# PERIPHERALS.net
KiCad netlist of a schematic drawn in Altium Designer
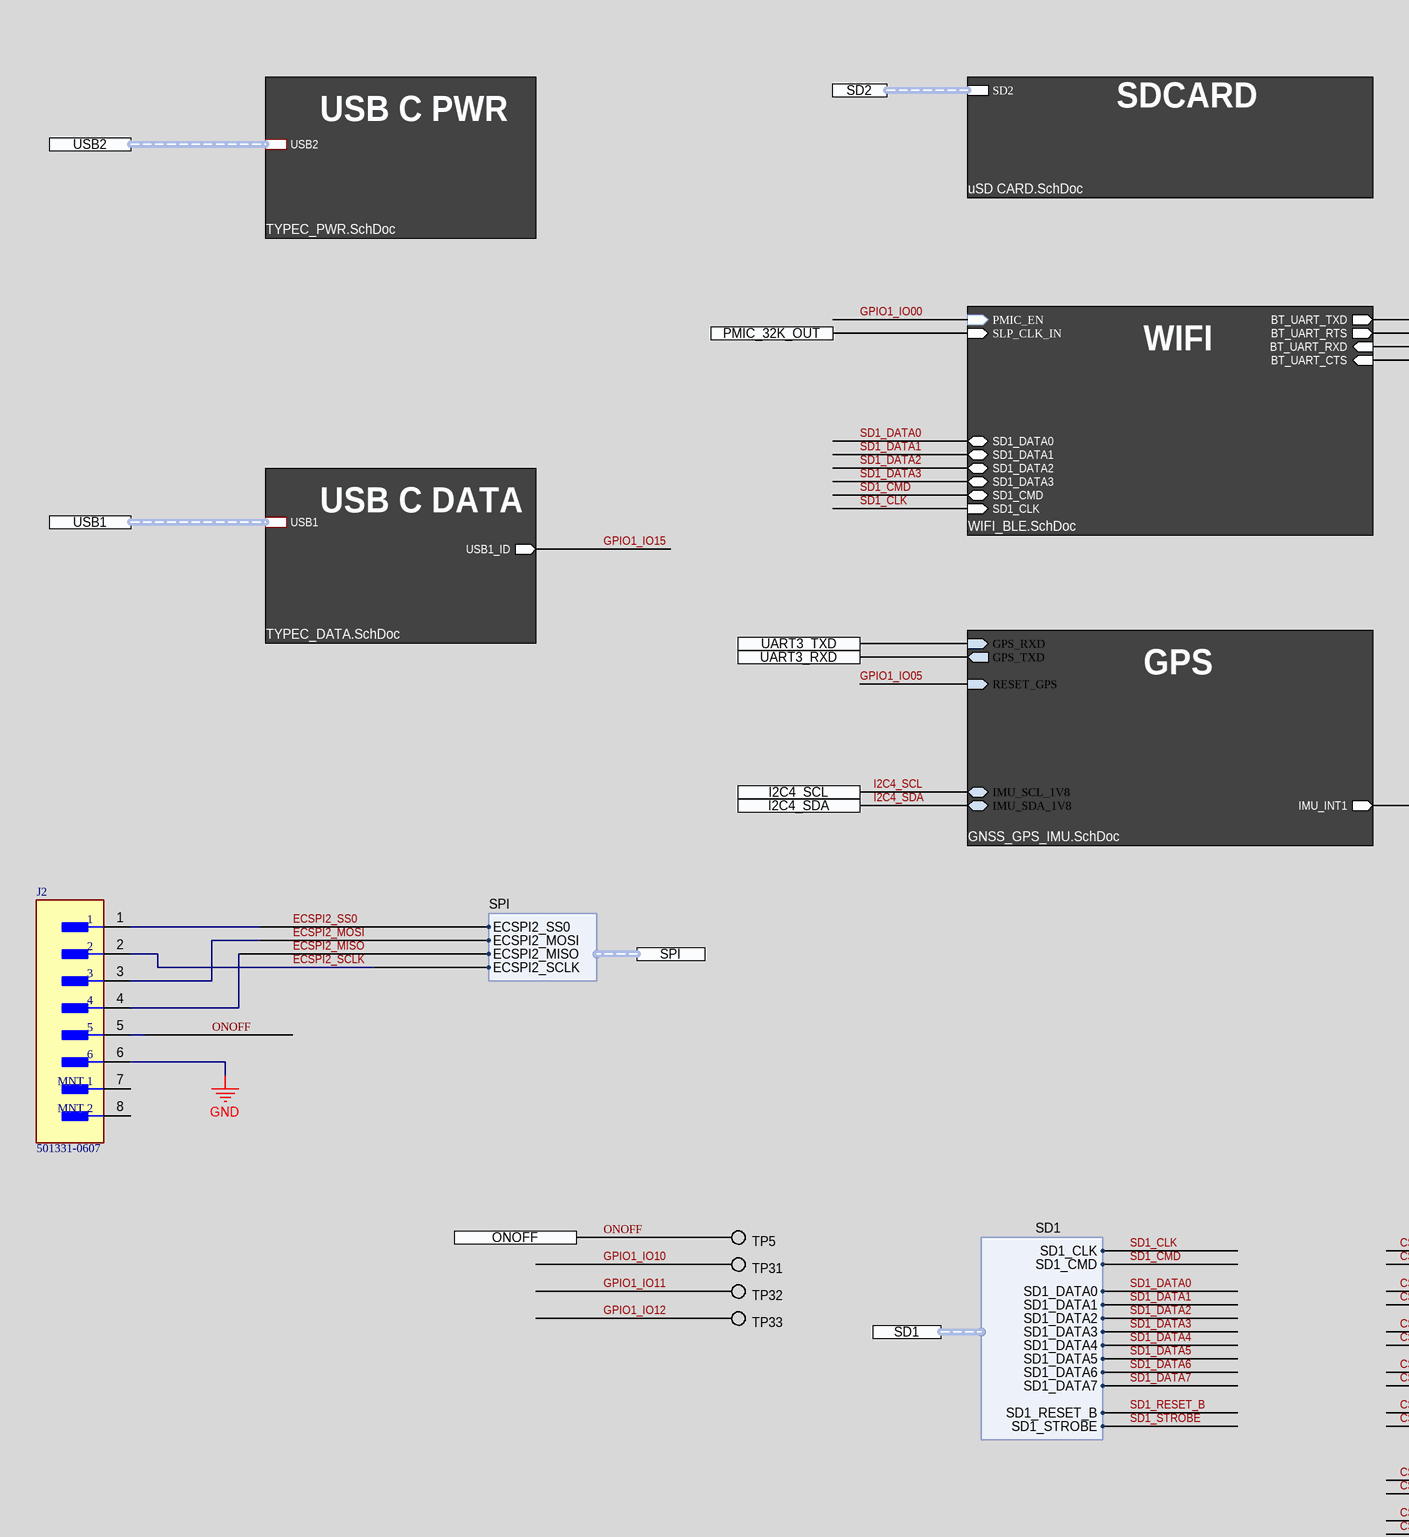
[diagram p0: PERIPHERALS.SchDoc, left]
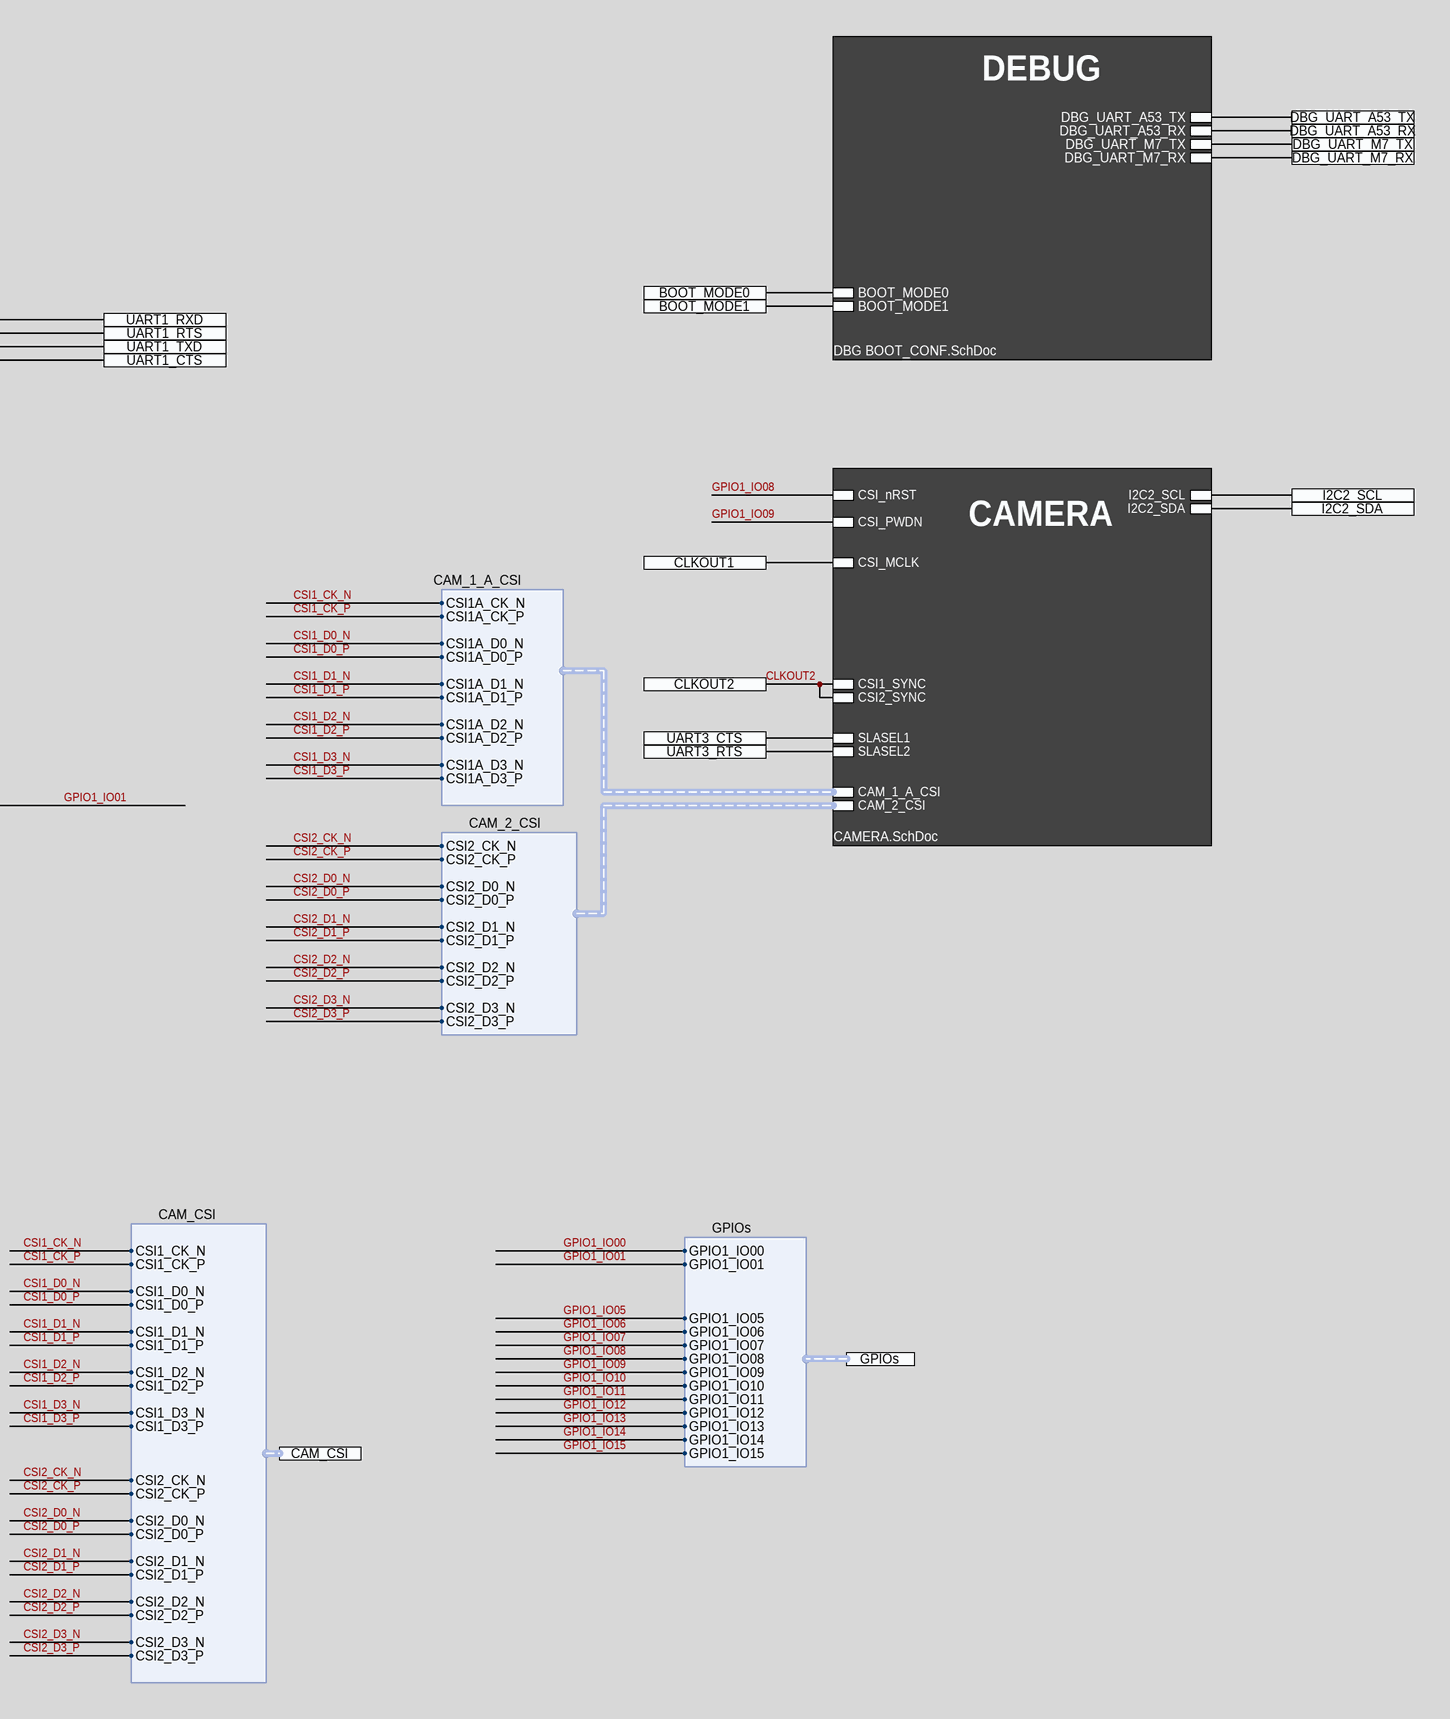
[diagram p1: PERIPHERALS.SchDoc, right]

(export (version "E")
  (design (tool "Eeschema 10.0.6"))
  (components
    (comp (ref "J2")
      (value "501331-0607")
      (footprint "FP-501331-0607-MFG")
      (description "CONN HEADER SMD 6POS 1MM")
      (libsource (lib "Altium Content Vault") (part "2bd7785e6f3406c6201afa29ba70f07"))
    )
    (comp (ref "TP5")
      (value "NO COMPONENT")
      (footprint "TP_PAD_0.5MM_SMD_ROUND")
      (description "Test Point, SMD pad, round, 1.5mm, 1.6mm, 3mm diameter")
      (libsource (lib "Electronic Devices_LIB") (part "TP_PAD_SMD_SMALL"))
    )
    (comp (ref "TP31")
      (value "NO COMPONENT")
      (footprint "TP_PAD_0.5MM_SMD_ROUND")
      (description "Test Point, SMD pad, round, 1.5mm, 1.6mm, 3mm diameter")
      (libsource (lib "Electronic Devices_LIB") (part "TP_PAD_SMD_SMALL"))
    )
    (comp (ref "TP32")
      (value "NO COMPONENT")
      (footprint "TP_PAD_0.5MM_SMD_ROUND")
      (description "Test Point, SMD pad, round, 1.5mm, 1.6mm, 3mm diameter")
      (libsource (lib "Electronic Devices_LIB") (part "TP_PAD_SMD_SMALL"))
    )
    (comp (ref "TP33")
      (value "NO COMPONENT")
      (footprint "TP_PAD_0.5MM_SMD_ROUND")
      (description "Test Point, SMD pad, round, 1.5mm, 1.6mm, 3mm diameter")
      (libsource (lib "Electronic Devices_LIB") (part "TP_PAD_SMD_SMALL"))
    )
  )
  (nets
    (net (code "38") (name "/ECSPI2_MISO") (class "Default")
      (node (ref "J2") (pin "4") (pinfunction "4_4") (pintype "passive"))
    )
    (net (code "39") (name "/ECSPI2_MOSI") (class "Default")
      (node (ref "J2") (pin "3") (pinfunction "3_3") (pintype "passive"))
    )
    (net (code "40") (name "/ECSPI2_SCLK") (class "Default")
      (node (ref "J2") (pin "2") (pinfunction "2_2") (pintype "passive"))
    )
    (net (code "41") (name "/ECSPI2_SS0") (class "Default")
      (node (ref "J2") (pin "1") (pinfunction "1_1") (pintype "passive"))
    )
    (net (code "49") (name "/GPIO1_IO10") (class "Default")
      (node (ref "TP31") (pin "1") (pinfunction "1_1") (pintype "passive"))
    )
    (net (code "50") (name "/GPIO1_IO11") (class "Default")
      (node (ref "TP32") (pin "1") (pinfunction "1_1") (pintype "passive"))
    )
    (net (code "51") (name "/GPIO1_IO12") (class "Default")
      (node (ref "TP33") (pin "1") (pinfunction "1_1") (pintype "passive"))
    )
    (net (code "59") (name "/ONOFF") (class "Default")
      (node (ref "J2") (pin "5") (pinfunction "5_5") (pintype "passive"))
      (node (ref "TP5") (pin "1") (pinfunction "1_1") (pintype "passive"))
    )
    (net (code "90") (name "GND") (class "Default")
      (node (ref "J2") (pin "6") (pinfunction "6_6") (pintype "passive"))
    )
    (net (code "91") (name "unconnected-(J2-MNT_1-Pad7)") (class "Default")
      (node (ref "J2") (pin "7") (pinfunction "MNT_1_7") (pintype "passive"))
    )
    (net (code "92") (name "unconnected-(J2-MNT_2-Pad8)") (class "Default")
      (node (ref "J2") (pin "8") (pinfunction "MNT_2_8") (pintype "passive"))
    )
  )
)
